# EIB32-JAE_MC-Av2.net
KiCad netlist of a schematic drawn in EAGLE
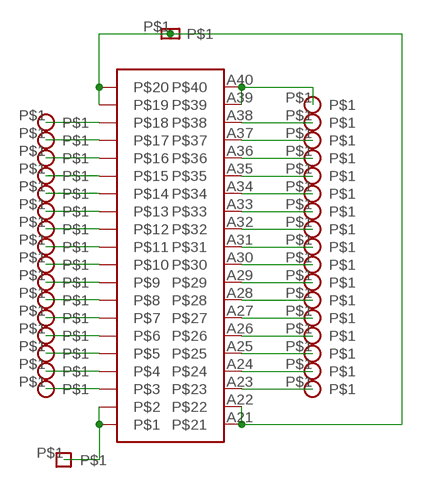
[diagram p0: schematic, sheet 1]

(export (version "E")
  (design (tool "Eeschema 10.0.6"))
  (components
    (comp (ref "U$1")
      (value "WR-40SB-VFH30")
      (footprint "eagle-import:WR-40SB-VFH30")
      (libsource (lib "eagle-import") (part "WR-40SB-VFH30"))
    )
    (comp (ref "U$2")
      (value "EIB-GND-HOLE-PAD-SMALL")
      (footprint "eagle-import:EIB-GND-HOLE-PAD-SMALL")
      (libsource (lib "eagle-import") (part "EIB-GND-HOLE-PAD-SMALL"))
    )
    (comp (ref "U$3")
      (value "EIB-GND-HOLE-PAD")
      (footprint "eagle-import:EIB-GND-HOLE-PAD")
      (libsource (lib "eagle-import") (part "EIB-GND-HOLE-PAD"))
    )
    (comp (ref "U$5")
      (value "EIB-TETRODE-HOLE-RS-PAD")
      (footprint "eagle-import:EIB-TETRODE-HOLE-RS-PAD")
      (libsource (lib "eagle-import") (part "EIB-TETRODE-HOLE-RS-PAD"))
    )
    (comp (ref "U$6")
      (value "EIB-TETRODE-HOLE-RS-PAD")
      (footprint "eagle-import:EIB-TETRODE-HOLE-RS-PAD")
      (libsource (lib "eagle-import") (part "EIB-TETRODE-HOLE-RS-PAD"))
    )
    (comp (ref "U$7")
      (value "EIB-TETRODE-HOLE-RS-PAD")
      (footprint "eagle-import:EIB-TETRODE-HOLE-RS-PAD")
      (libsource (lib "eagle-import") (part "EIB-TETRODE-HOLE-RS-PAD"))
    )
    (comp (ref "U$8")
      (value "EIB-TETRODE-HOLE-RS-PAD")
      (footprint "eagle-import:EIB-TETRODE-HOLE-RS-PAD")
      (libsource (lib "eagle-import") (part "EIB-TETRODE-HOLE-RS-PAD"))
    )
    (comp (ref "U$9")
      (value "EIB-TETRODE-HOLE-RS-PAD")
      (footprint "eagle-import:EIB-TETRODE-HOLE-RS-PAD")
      (libsource (lib "eagle-import") (part "EIB-TETRODE-HOLE-RS-PAD"))
    )
    (comp (ref "U$10")
      (value "EIB-TETRODE-HOLE-RS-PAD")
      (footprint "eagle-import:EIB-TETRODE-HOLE-RS-PAD")
      (libsource (lib "eagle-import") (part "EIB-TETRODE-HOLE-RS-PAD"))
    )
    (comp (ref "U$11")
      (value "EIB-TETRODE-HOLE-RS-PAD")
      (footprint "eagle-import:EIB-TETRODE-HOLE-RS-PAD")
      (libsource (lib "eagle-import") (part "EIB-TETRODE-HOLE-RS-PAD"))
    )
    (comp (ref "U$12")
      (value "EIB-TETRODE-HOLE-RS-PAD")
      (footprint "eagle-import:EIB-TETRODE-HOLE-RS-PAD")
      (libsource (lib "eagle-import") (part "EIB-TETRODE-HOLE-RS-PAD"))
    )
    (comp (ref "U$13")
      (value "EIB-TETRODE-HOLE-RS-PAD")
      (footprint "eagle-import:EIB-TETRODE-HOLE-RS-PAD")
      (libsource (lib "eagle-import") (part "EIB-TETRODE-HOLE-RS-PAD"))
    )
    (comp (ref "U$14")
      (value "EIB-TETRODE-HOLE-RS-PAD")
      (footprint "eagle-import:EIB-TETRODE-HOLE-RS-PAD")
      (libsource (lib "eagle-import") (part "EIB-TETRODE-HOLE-RS-PAD"))
    )
    (comp (ref "U$15")
      (value "EIB-TETRODE-HOLE-RS-PAD")
      (footprint "eagle-import:EIB-TETRODE-HOLE-RS-PAD")
      (libsource (lib "eagle-import") (part "EIB-TETRODE-HOLE-RS-PAD"))
    )
    (comp (ref "U$16")
      (value "EIB-TETRODE-HOLE-RS-PAD")
      (footprint "eagle-import:EIB-TETRODE-HOLE-RS-PAD")
      (libsource (lib "eagle-import") (part "EIB-TETRODE-HOLE-RS-PAD"))
    )
    (comp (ref "U$17")
      (value "EIB-TETRODE-HOLE-RS-PAD")
      (footprint "eagle-import:EIB-TETRODE-HOLE-RS-PAD")
      (libsource (lib "eagle-import") (part "EIB-TETRODE-HOLE-RS-PAD"))
    )
    (comp (ref "U$18")
      (value "EIB-TETRODE-HOLE-RS-PAD")
      (footprint "eagle-import:EIB-TETRODE-HOLE-RS-PAD")
      (libsource (lib "eagle-import") (part "EIB-TETRODE-HOLE-RS-PAD"))
    )
    (comp (ref "U$19")
      (value "EIB-TETRODE-HOLE-RS-PAD")
      (footprint "eagle-import:EIB-TETRODE-HOLE-RS-PAD")
      (libsource (lib "eagle-import") (part "EIB-TETRODE-HOLE-RS-PAD"))
    )
    (comp (ref "U$20")
      (value "EIB-TETRODE-HOLE-RS-PAD")
      (footprint "eagle-import:EIB-TETRODE-HOLE-RS-PAD")
      (libsource (lib "eagle-import") (part "EIB-TETRODE-HOLE-RS-PAD"))
    )
    (comp (ref "U$22")
      (value "EIB-TETRODE-HOLE-RS-PAD")
      (footprint "eagle-import:EIB-TETRODE-HOLE-RS-PAD")
      (libsource (lib "eagle-import") (part "EIB-TETRODE-HOLE-RS-PAD"))
    )
    (comp (ref "U$23")
      (value "EIB-TETRODE-HOLE-RS-PAD")
      (footprint "eagle-import:EIB-TETRODE-HOLE-RS-PAD")
      (libsource (lib "eagle-import") (part "EIB-TETRODE-HOLE-RS-PAD"))
    )
    (comp (ref "U$24")
      (value "EIB-TETRODE-HOLE-RS-PAD")
      (footprint "eagle-import:EIB-TETRODE-HOLE-RS-PAD")
      (libsource (lib "eagle-import") (part "EIB-TETRODE-HOLE-RS-PAD"))
    )
    (comp (ref "U$25")
      (value "EIB-TETRODE-HOLE-RS-PAD")
      (footprint "eagle-import:EIB-TETRODE-HOLE-RS-PAD")
      (libsource (lib "eagle-import") (part "EIB-TETRODE-HOLE-RS-PAD"))
    )
    (comp (ref "U$26")
      (value "EIB-TETRODE-HOLE-RS-PAD")
      (footprint "eagle-import:EIB-TETRODE-HOLE-RS-PAD")
      (libsource (lib "eagle-import") (part "EIB-TETRODE-HOLE-RS-PAD"))
    )
    (comp (ref "U$27")
      (value "EIB-TETRODE-HOLE-RS-PAD")
      (footprint "eagle-import:EIB-TETRODE-HOLE-RS-PAD")
      (libsource (lib "eagle-import") (part "EIB-TETRODE-HOLE-RS-PAD"))
    )
    (comp (ref "U$28")
      (value "EIB-TETRODE-HOLE-RS-PAD")
      (footprint "eagle-import:EIB-TETRODE-HOLE-RS-PAD")
      (libsource (lib "eagle-import") (part "EIB-TETRODE-HOLE-RS-PAD"))
    )
    (comp (ref "U$29")
      (value "EIB-TETRODE-HOLE-RS-PAD")
      (footprint "eagle-import:EIB-TETRODE-HOLE-RS-PAD")
      (libsource (lib "eagle-import") (part "EIB-TETRODE-HOLE-RS-PAD"))
    )
    (comp (ref "U$30")
      (value "EIB-TETRODE-HOLE-RS-PAD")
      (footprint "eagle-import:EIB-TETRODE-HOLE-RS-PAD")
      (libsource (lib "eagle-import") (part "EIB-TETRODE-HOLE-RS-PAD"))
    )
    (comp (ref "U$31")
      (value "EIB-TETRODE-HOLE-RS-PAD")
      (footprint "eagle-import:EIB-TETRODE-HOLE-RS-PAD")
      (libsource (lib "eagle-import") (part "EIB-TETRODE-HOLE-RS-PAD"))
    )
    (comp (ref "U$32")
      (value "EIB-TETRODE-HOLE-RS-PAD")
      (footprint "eagle-import:EIB-TETRODE-HOLE-RS-PAD")
      (libsource (lib "eagle-import") (part "EIB-TETRODE-HOLE-RS-PAD"))
    )
    (comp (ref "U$33")
      (value "EIB-TETRODE-HOLE-RS-PAD")
      (footprint "eagle-import:EIB-TETRODE-HOLE-RS-PAD")
      (libsource (lib "eagle-import") (part "EIB-TETRODE-HOLE-RS-PAD"))
    )
    (comp (ref "U$34")
      (value "EIB-TETRODE-HOLE-RS-PAD")
      (footprint "eagle-import:EIB-TETRODE-HOLE-RS-PAD")
      (libsource (lib "eagle-import") (part "EIB-TETRODE-HOLE-RS-PAD"))
    )
    (comp (ref "U$35")
      (value "EIB-TETRODE-HOLE-RS-PAD")
      (footprint "eagle-import:EIB-TETRODE-HOLE-RS-PAD")
      (libsource (lib "eagle-import") (part "EIB-TETRODE-HOLE-RS-PAD"))
    )
    (comp (ref "U$36")
      (value "EIB-TETRODE-HOLE-RS-PAD")
      (footprint "eagle-import:EIB-TETRODE-HOLE-RS-PAD")
      (libsource (lib "eagle-import") (part "EIB-TETRODE-HOLE-RS-PAD"))
    )
    (comp (ref "U$37")
      (value "EIB-TETRODE-HOLE-RS-PAD")
      (footprint "eagle-import:EIB-TETRODE-HOLE-RS-PAD")
      (libsource (lib "eagle-import") (part "EIB-TETRODE-HOLE-RS-PAD"))
    )
    (comp (ref "U$38")
      (value "EIB-TETRODE-HOLE-RS-PAD")
      (footprint "eagle-import:EIB-TETRODE-HOLE-RS-PAD")
      (libsource (lib "eagle-import") (part "EIB-TETRODE-HOLE-RS-PAD"))
    )
  )
  (nets
    (net (code "1") (name "Net-(U$1-P$1)") (class "Default")
      (node (ref "U$1") (pin "A1") (pinfunction "P$1_A1") (pintype "bidirectional"))
      (node (ref "U$1") (pin "A2") (pinfunction "P$2_A2") (pintype "bidirectional"))
      (node (ref "U$3") (pin "P$1") (pinfunction "P$1_P$1") (pintype "bidirectional"))
    )
    (net (code "2") (name "Net-(U$1-P$3)") (class "Default")
      (node (ref "U$1") (pin "A3") (pinfunction "P$3_A3") (pintype "bidirectional"))
      (node (ref "U$20") (pin "P$1") (pinfunction "P$1_P$1") (pintype "bidirectional"))
    )
    (net (code "3") (name "Net-(U$1-P$4)") (class "Default")
      (node (ref "U$1") (pin "A4") (pinfunction "P$4_A4") (pintype "bidirectional"))
      (node (ref "U$19") (pin "P$1") (pinfunction "P$1_P$1") (pintype "bidirectional"))
    )
    (net (code "4") (name "Net-(U$1-P$5)") (class "Default")
      (node (ref "U$1") (pin "A5") (pinfunction "P$5_A5") (pintype "bidirectional"))
      (node (ref "U$18") (pin "P$1") (pinfunction "P$1_P$1") (pintype "bidirectional"))
    )
    (net (code "5") (name "Net-(U$1-P$6)") (class "Default")
      (node (ref "U$1") (pin "A6") (pinfunction "P$6_A6") (pintype "bidirectional"))
      (node (ref "U$17") (pin "P$1") (pinfunction "P$1_P$1") (pintype "bidirectional"))
    )
    (net (code "6") (name "Net-(U$1-P$7)") (class "Default")
      (node (ref "U$1") (pin "A7") (pinfunction "P$7_A7") (pintype "bidirectional"))
      (node (ref "U$16") (pin "P$1") (pinfunction "P$1_P$1") (pintype "bidirectional"))
    )
    (net (code "7") (name "Net-(U$1-P$8)") (class "Default")
      (node (ref "U$1") (pin "A8") (pinfunction "P$8_A8") (pintype "bidirectional"))
      (node (ref "U$15") (pin "P$1") (pinfunction "P$1_P$1") (pintype "bidirectional"))
    )
    (net (code "8") (name "Net-(U$1-P$9)") (class "Default")
      (node (ref "U$1") (pin "A9") (pinfunction "P$9_A9") (pintype "bidirectional"))
      (node (ref "U$14") (pin "P$1") (pinfunction "P$1_P$1") (pintype "bidirectional"))
    )
    (net (code "9") (name "Net-(U$1-P$10)") (class "Default")
      (node (ref "U$1") (pin "A10") (pinfunction "P$10_A10") (pintype "bidirectional"))
      (node (ref "U$13") (pin "P$1") (pinfunction "P$1_P$1") (pintype "bidirectional"))
    )
    (net (code "10") (name "Net-(U$1-P$11)") (class "Default")
      (node (ref "U$1") (pin "A11") (pinfunction "P$11_A11") (pintype "bidirectional"))
      (node (ref "U$12") (pin "P$1") (pinfunction "P$1_P$1") (pintype "bidirectional"))
    )
    (net (code "11") (name "Net-(U$1-P$12)") (class "Default")
      (node (ref "U$1") (pin "A12") (pinfunction "P$12_A12") (pintype "bidirectional"))
      (node (ref "U$11") (pin "P$1") (pinfunction "P$1_P$1") (pintype "bidirectional"))
    )
    (net (code "12") (name "Net-(U$1-P$13)") (class "Default")
      (node (ref "U$1") (pin "A13") (pinfunction "P$13_A13") (pintype "bidirectional"))
      (node (ref "U$10") (pin "P$1") (pinfunction "P$1_P$1") (pintype "bidirectional"))
    )
    (net (code "13") (name "Net-(U$1-P$14)") (class "Default")
      (node (ref "U$1") (pin "A14") (pinfunction "P$14_A14") (pintype "bidirectional"))
      (node (ref "U$9") (pin "P$1") (pinfunction "P$1_P$1") (pintype "bidirectional"))
    )
    (net (code "14") (name "Net-(U$1-P$15)") (class "Default")
      (node (ref "U$1") (pin "A15") (pinfunction "P$15_A15") (pintype "bidirectional"))
      (node (ref "U$8") (pin "P$1") (pinfunction "P$1_P$1") (pintype "bidirectional"))
    )
    (net (code "15") (name "Net-(U$1-P$16)") (class "Default")
      (node (ref "U$1") (pin "A16") (pinfunction "P$16_A16") (pintype "bidirectional"))
      (node (ref "U$7") (pin "P$1") (pinfunction "P$1_P$1") (pintype "bidirectional"))
    )
    (net (code "16") (name "Net-(U$1-P$17)") (class "Default")
      (node (ref "U$1") (pin "A17") (pinfunction "P$17_A17") (pintype "bidirectional"))
      (node (ref "U$6") (pin "P$1") (pinfunction "P$1_P$1") (pintype "bidirectional"))
    )
    (net (code "17") (name "Net-(U$1-P$18)") (class "Default")
      (node (ref "U$1") (pin "A18") (pinfunction "P$18_A18") (pintype "bidirectional"))
      (node (ref "U$5") (pin "P$1") (pinfunction "P$1_P$1") (pintype "bidirectional"))
    )
    (net (code "18") (name "Net-(U$1-P$19)") (class "Default")
      (node (ref "U$1") (pin "A19") (pinfunction "P$19_A19") (pintype "bidirectional"))
      (node (ref "U$1") (pin "A20") (pinfunction "P$20_A20") (pintype "bidirectional"))
      (node (ref "U$1") (pin "A21") (pinfunction "P$21_A21") (pintype "bidirectional"))
      (node (ref "U$1") (pin "A22") (pinfunction "P$22_A22") (pintype "bidirectional"))
      (node (ref "U$2") (pin "P$1") (pinfunction "P$1_P$1") (pintype "bidirectional"))
    )
    (net (code "19") (name "Net-(U$1-P$23)") (class "Default")
      (node (ref "U$1") (pin "A23") (pinfunction "P$23_A23") (pintype "bidirectional"))
      (node (ref "U$38") (pin "P$1") (pinfunction "P$1_P$1") (pintype "bidirectional"))
    )
    (net (code "20") (name "Net-(U$1-P$24)") (class "Default")
      (node (ref "U$1") (pin "A24") (pinfunction "P$24_A24") (pintype "bidirectional"))
      (node (ref "U$37") (pin "P$1") (pinfunction "P$1_P$1") (pintype "bidirectional"))
    )
    (net (code "21") (name "Net-(U$1-P$25)") (class "Default")
      (node (ref "U$1") (pin "A25") (pinfunction "P$25_A25") (pintype "bidirectional"))
      (node (ref "U$36") (pin "P$1") (pinfunction "P$1_P$1") (pintype "bidirectional"))
    )
    (net (code "22") (name "Net-(U$1-P$26)") (class "Default")
      (node (ref "U$1") (pin "A26") (pinfunction "P$26_A26") (pintype "bidirectional"))
      (node (ref "U$35") (pin "P$1") (pinfunction "P$1_P$1") (pintype "bidirectional"))
    )
    (net (code "23") (name "Net-(U$1-P$27)") (class "Default")
      (node (ref "U$1") (pin "A27") (pinfunction "P$27_A27") (pintype "bidirectional"))
      (node (ref "U$34") (pin "P$1") (pinfunction "P$1_P$1") (pintype "bidirectional"))
    )
    (net (code "24") (name "Net-(U$1-P$28)") (class "Default")
      (node (ref "U$1") (pin "A28") (pinfunction "P$28_A28") (pintype "bidirectional"))
      (node (ref "U$33") (pin "P$1") (pinfunction "P$1_P$1") (pintype "bidirectional"))
    )
    (net (code "25") (name "Net-(U$1-P$29)") (class "Default")
      (node (ref "U$1") (pin "A29") (pinfunction "P$29_A29") (pintype "bidirectional"))
      (node (ref "U$32") (pin "P$1") (pinfunction "P$1_P$1") (pintype "bidirectional"))
    )
    (net (code "26") (name "Net-(U$1-P$30)") (class "Default")
      (node (ref "U$1") (pin "A30") (pinfunction "P$30_A30") (pintype "bidirectional"))
      (node (ref "U$31") (pin "P$1") (pinfunction "P$1_P$1") (pintype "bidirectional"))
    )
    (net (code "27") (name "Net-(U$1-P$31)") (class "Default")
      (node (ref "U$1") (pin "A31") (pinfunction "P$31_A31") (pintype "bidirectional"))
      (node (ref "U$30") (pin "P$1") (pinfunction "P$1_P$1") (pintype "bidirectional"))
    )
    (net (code "28") (name "Net-(U$1-P$32)") (class "Default")
      (node (ref "U$1") (pin "A32") (pinfunction "P$32_A32") (pintype "bidirectional"))
      (node (ref "U$29") (pin "P$1") (pinfunction "P$1_P$1") (pintype "bidirectional"))
    )
    (net (code "29") (name "Net-(U$1-P$33)") (class "Default")
      (node (ref "U$1") (pin "A33") (pinfunction "P$33_A33") (pintype "bidirectional"))
      (node (ref "U$28") (pin "P$1") (pinfunction "P$1_P$1") (pintype "bidirectional"))
    )
    (net (code "30") (name "Net-(U$1-P$34)") (class "Default")
      (node (ref "U$1") (pin "A34") (pinfunction "P$34_A34") (pintype "bidirectional"))
      (node (ref "U$27") (pin "P$1") (pinfunction "P$1_P$1") (pintype "bidirectional"))
    )
    (net (code "31") (name "Net-(U$1-P$35)") (class "Default")
      (node (ref "U$1") (pin "A35") (pinfunction "P$35_A35") (pintype "bidirectional"))
      (node (ref "U$26") (pin "P$1") (pinfunction "P$1_P$1") (pintype "bidirectional"))
    )
    (net (code "32") (name "Net-(U$1-P$36)") (class "Default")
      (node (ref "U$1") (pin "A36") (pinfunction "P$36_A36") (pintype "bidirectional"))
      (node (ref "U$25") (pin "P$1") (pinfunction "P$1_P$1") (pintype "bidirectional"))
    )
    (net (code "33") (name "Net-(U$1-P$37)") (class "Default")
      (node (ref "U$1") (pin "A37") (pinfunction "P$37_A37") (pintype "bidirectional"))
      (node (ref "U$24") (pin "P$1") (pinfunction "P$1_P$1") (pintype "bidirectional"))
    )
    (net (code "34") (name "Net-(U$1-P$38)") (class "Default")
      (node (ref "U$1") (pin "A38") (pinfunction "P$38_A38") (pintype "bidirectional"))
      (node (ref "U$23") (pin "P$1") (pinfunction "P$1_P$1") (pintype "bidirectional"))
    )
    (net (code "35") (name "Net-(U$1-P$39)") (class "Default")
      (node (ref "U$1") (pin "A39") (pinfunction "P$39_A39") (pintype "bidirectional"))
      (node (ref "U$1") (pin "A40") (pinfunction "P$40_A40") (pintype "bidirectional"))
      (node (ref "U$22") (pin "P$1") (pinfunction "P$1_P$1") (pintype "bidirectional"))
    )
  )
)
